# MK_0_2.net
KiCad netlist of a schematic drawn in Altium Designer
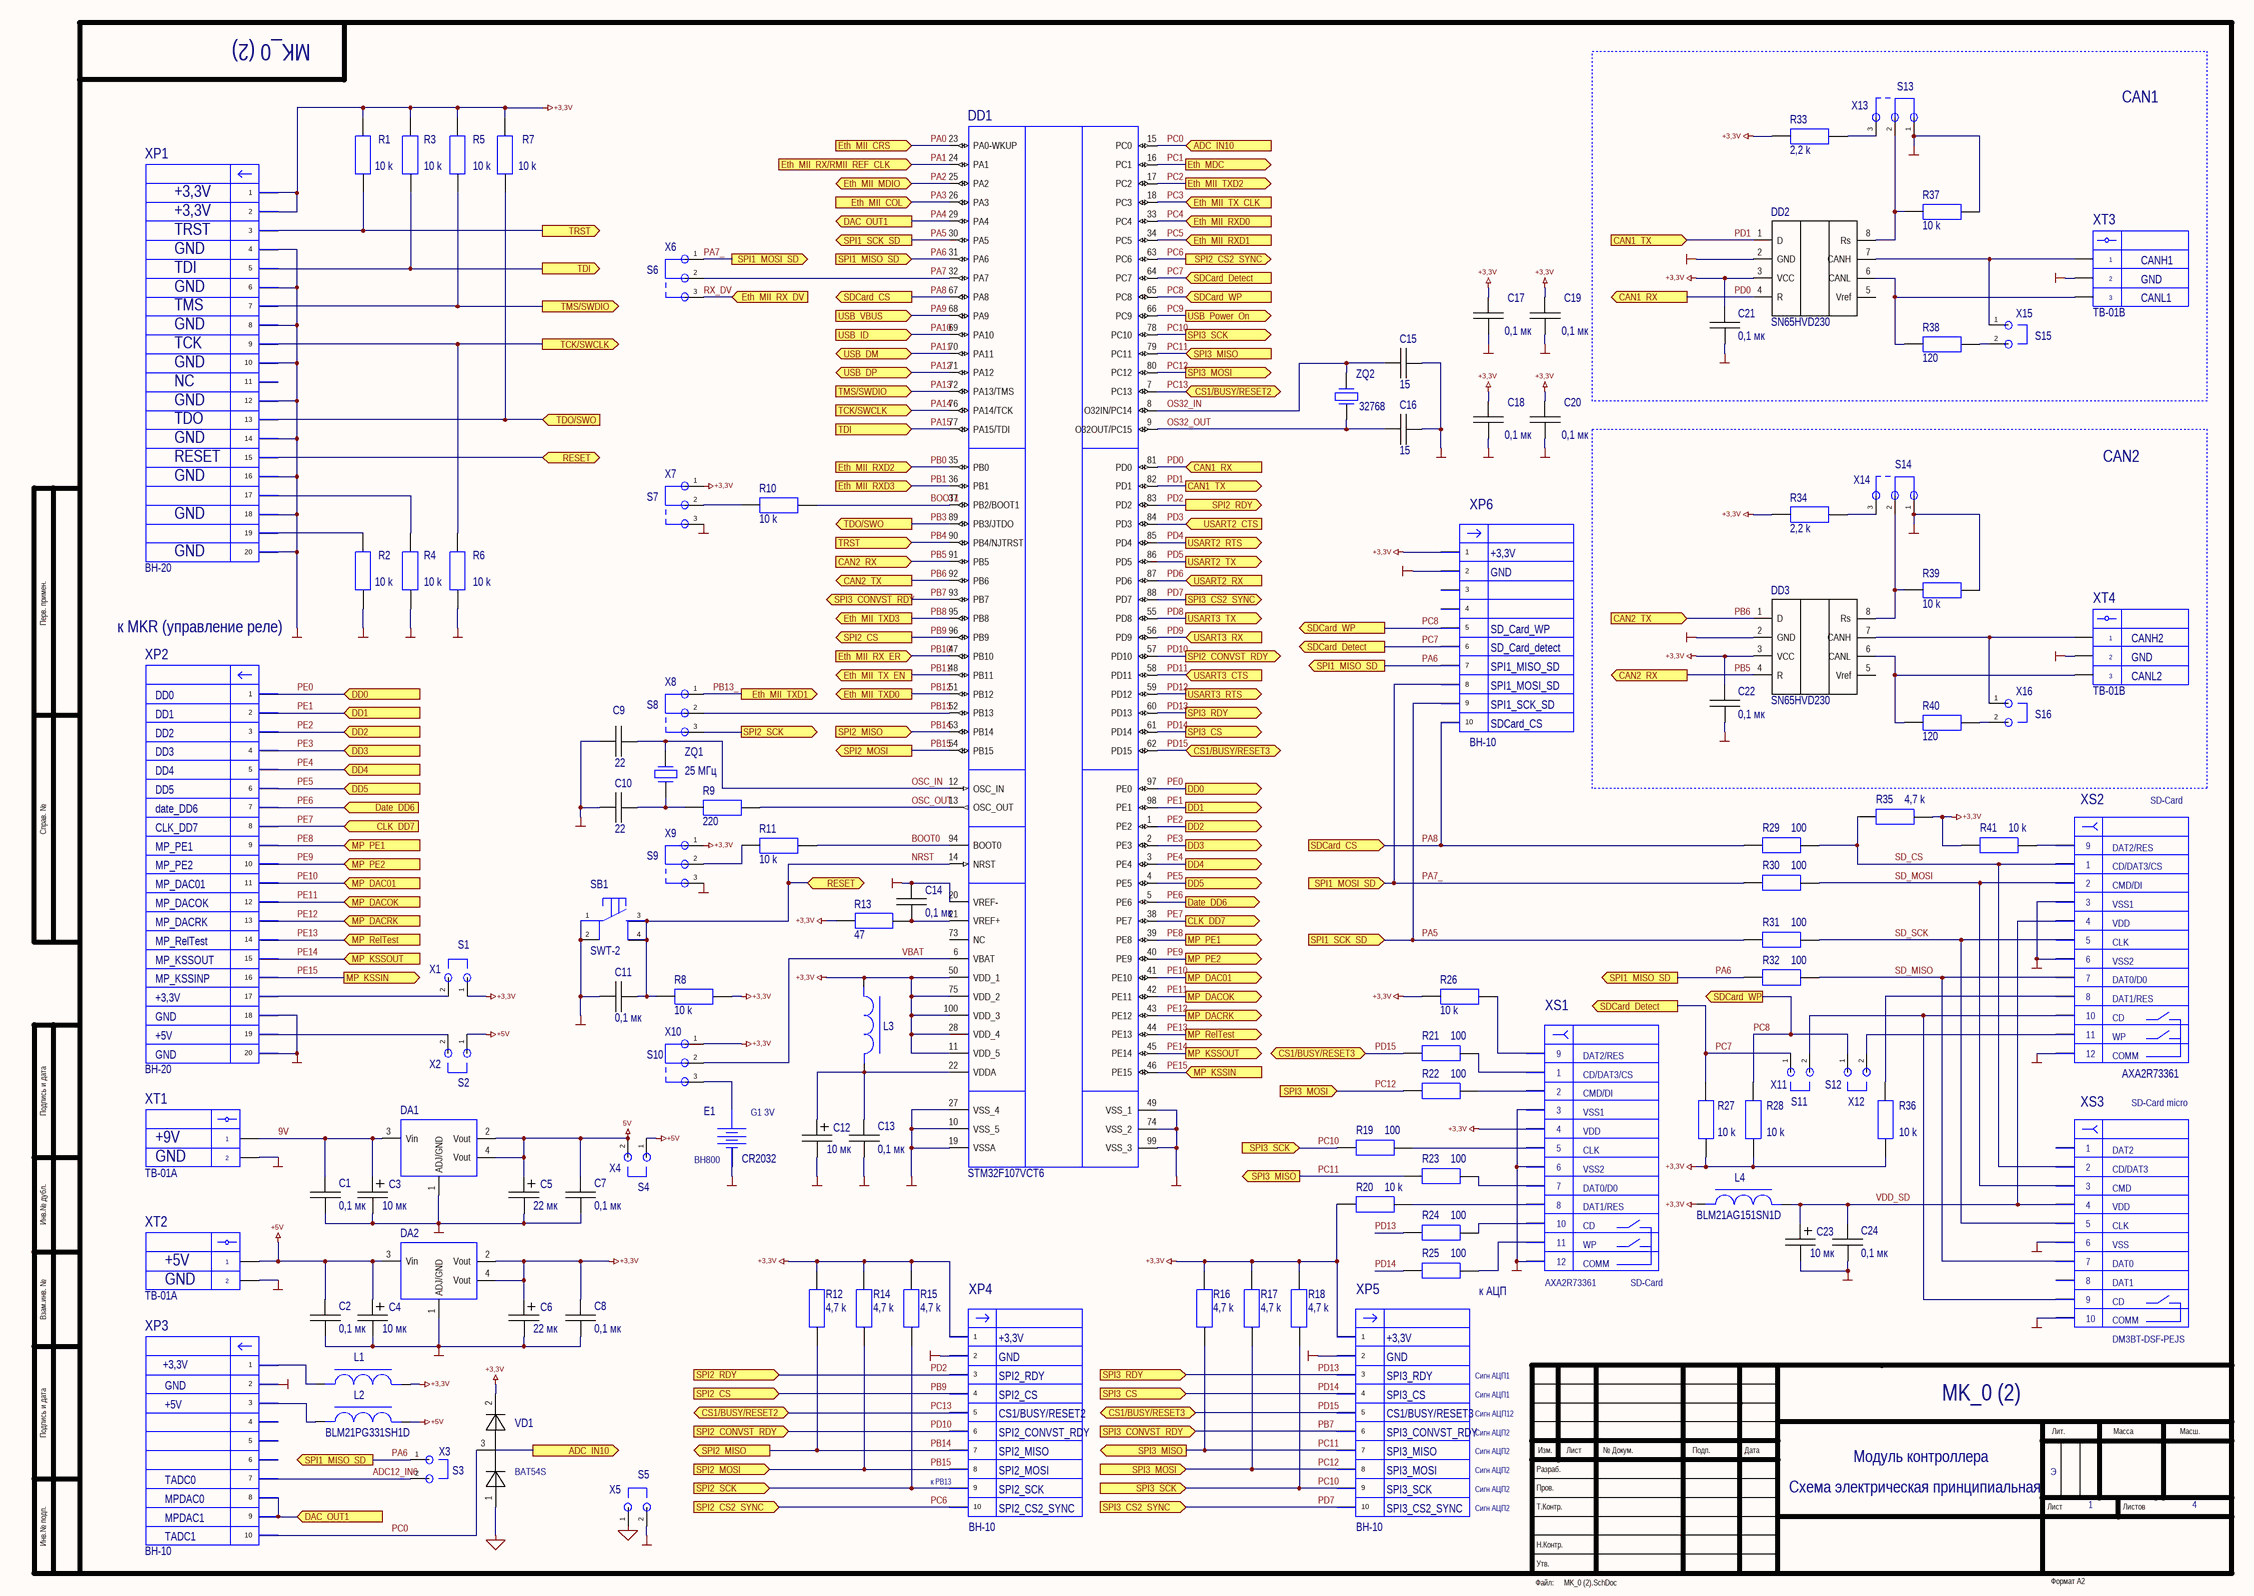
[diagram p0: MK_0 (2).SchDoc]

(export (version "E")
  (design (tool "Eeschema 10.0.6"))
  (components
    (comp (ref "C1")
      (value "0,1 мк")
      (footprint "CAPC_1206")
      (description "Capasitor")
      (fields (field (name "PART NUMBER") "C"))
      (libsource (lib "RLC_GOST") (part "C"))
    )
    (comp (ref "C2")
      (value "0,1 мк")
      (footprint "CAPC_1206")
      (description "Capasitor")
      (fields (field (name "PART NUMBER") "C"))
      (libsource (lib "RLC_GOST") (part "C"))
    )
    (comp (ref "C3")
      (value "10 мк")
      (footprint "3216")
      (description "Capasitor_polar")
      (fields (field (name "PART NUMBER") "CapPol"))
      (libsource (lib "RLC_GOST") (part "CapPol"))
    )
    (comp (ref "C4")
      (value "10 мк")
      (footprint "3216")
      (description "Capasitor_polar")
      (fields (field (name "PART NUMBER") "CapPol"))
      (libsource (lib "RLC_GOST") (part "CapPol"))
    )
    (comp (ref "C5")
      (value "22 мк")
      (footprint "3216")
      (description "Capasitor_polar")
      (fields (field (name "PART NUMBER") "CapPol"))
      (libsource (lib "RLC_GOST") (part "CapPol"))
    )
    (comp (ref "C6")
      (value "22 мк")
      (footprint "3216")
      (description "Capasitor_polar")
      (fields (field (name "PART NUMBER") "CapPol"))
      (libsource (lib "RLC_GOST") (part "CapPol"))
    )
    (comp (ref "C7")
      (value "0,1 мк")
      (footprint "CAPC_1206")
      (description "Capasitor")
      (fields (field (name "PART NUMBER") "C"))
      (libsource (lib "RLC_GOST") (part "C"))
    )
    (comp (ref "C8")
      (value "0,1 мк")
      (footprint "CAPC_1206")
      (description "Capasitor")
      (fields (field (name "PART NUMBER") "C"))
      (libsource (lib "RLC_GOST") (part "C"))
    )
    (comp (ref "C9")
      (value "22")
      (footprint "CAPC_1206")
      (description "Capasitor")
      (libsource (lib "RLC_GOST") (part "C"))
    )
    (comp (ref "C10")
      (value "22")
      (footprint "CAPC_1206")
      (description "Capasitor")
      (libsource (lib "RLC_GOST") (part "C"))
    )
    (comp (ref "C11")
      (value "0,1 мк")
      (footprint "CAPC_1206")
      (description "Capasitor")
      (libsource (lib "RLC_GOST") (part "C"))
    )
    (comp (ref "C12")
      (value "10 мк")
      (footprint "3216")
      (description "Capasitor_polar")
      (fields (field (name "PART NUMBER") "CapPol"))
      (libsource (lib "RLC_GOST") (part "CapPol"))
    )
    (comp (ref "C13")
      (value "0,1 мк")
      (footprint "CAPC_1206")
      (description "Capasitor")
      (fields (field (name "PART NUMBER") "C"))
      (libsource (lib "RLC_GOST") (part "C"))
    )
    (comp (ref "C14")
      (value "0,1 мк")
      (footprint "CAPC_1206")
      (description "Capasitor")
      (fields (field (name "PART NUMBER") "C"))
      (libsource (lib "RLC_GOST") (part "C"))
    )
    (comp (ref "C15")
      (value "15")
      (footprint "CAPC_1206")
      (description "Capasitor")
      (libsource (lib "RLC_GOST") (part "C"))
    )
    (comp (ref "C16")
      (value "15")
      (footprint "CAPC_1206")
      (description "Capasitor")
      (libsource (lib "RLC_GOST") (part "C"))
    )
    (comp (ref "C17")
      (value "0,1 мк")
      (footprint "CAPC_1206")
      (description "Capasitor")
      (fields (field (name "PART NUMBER") "C"))
      (libsource (lib "RLC_GOST") (part "C"))
    )
    (comp (ref "C18")
      (value "0,1 мк")
      (footprint "CAPC_1206")
      (description "Capasitor")
      (fields (field (name "PART NUMBER") "C"))
      (libsource (lib "RLC_GOST") (part "C"))
    )
    (comp (ref "C19")
      (value "0,1 мк")
      (footprint "CAPC_1206")
      (description "Capasitor")
      (fields (field (name "PART NUMBER") "C"))
      (libsource (lib "RLC_GOST") (part "C"))
    )
    (comp (ref "C20")
      (value "0,1 мк")
      (footprint "CAPC_1206")
      (description "Capasitor")
      (fields (field (name "PART NUMBER") "C"))
      (libsource (lib "RLC_GOST") (part "C"))
    )
    (comp (ref "C21")
      (value "0,1 мк")
      (footprint "CAPC_1206")
      (description "Capasitor")
      (fields (field (name "PART NUMBER") "C"))
      (libsource (lib "RLC_GOST") (part "C"))
    )
    (comp (ref "C22")
      (value "0,1 мк")
      (footprint "CAPC_1206")
      (description "Capasitor")
      (fields (field (name "PART NUMBER") "C"))
      (libsource (lib "RLC_GOST") (part "C"))
    )
    (comp (ref "C23")
      (value "10 мк")
      (footprint "3216")
      (description "Capasitor_polar")
      (fields (field (name "PART NUMBER") "CapPol"))
      (libsource (lib "RLC_GOST") (part "CapPol"))
    )
    (comp (ref "C24")
      (value "0,1 мк")
      (footprint "CAPC_1206")
      (description "Capasitor")
      (fields (field (name "PART NUMBER") "C"))
      (libsource (lib "RLC_GOST") (part "C"))
    )
    (comp (ref "DA1")
      (value "LM1117")
      (footprint "SOT223")
      (description "Positive voltage regulators")
      (fields (field (name "MANUFACTURER") "National Semiconductor"))
      (libsource (lib "Stabil") (part "LM1117"))
    )
    (comp (ref "DA2")
      (value "LM1117")
      (footprint "SOT223")
      (description "Positive voltage regulators")
      (fields (field (name "MANUFACTURER") "National Semiconductor"))
      (libsource (lib "Stabil") (part "LM1117"))
    )
    (comp (ref "DD1")
      (value "STM32F107VCT6")
      (footprint "LQFP100")
      (description "STM32 ARM-based 32-bit MCU with 256 Kbytes Flash, 100-pin LQFP, Industrial Temperature")
      (fields (field (name "PUBLISHER") "Altium Limited"))
      (libsource (lib "STM32") (part "STM32F107VCT6"))
    )
    (comp (ref "DD2")
      (value "SN65HVD230")
      (footprint "SO8")
      (description "CAN transceivers")
      (libsource (lib "CAN") (part "SN65HVD230"))
    )
    (comp (ref "DD3")
      (value "SN65HVD230")
      (footprint "SO8")
      (description "CAN transceivers")
      (libsource (lib "CAN") (part "SN65HVD230"))
    )
    (comp (ref "E1")
      (value "BH800")
      (footprint "BATTERY_20mm")
      (fields (field (name "ALTIUM_VALUE") "CR2032") (field (name "G") "G1 3V"))
      (libsource (lib "Connectors") (part "BH800"))
    )
    (comp (ref "L1")
      (value "BLM21PG331SH1D")
      (footprint "C0805")
      (description "Ferrite bead")
      (libsource (lib "RLC_GOST") (part "B"))
    )
    (comp (ref "L2")
      (value "BLM21PG331SH1D")
      (footprint "C0805")
      (description "Ferrite bead")
      (libsource (lib "RLC_GOST") (part "B"))
    )
    (comp (ref "L3")
      (value "BLM21AG151SN1D")
      (footprint "C0805")
      (description "Ferrite bead")
      (libsource (lib "RLC_GOST") (part "B"))
    )
    (comp (ref "L4")
      (value "BLM21AG151SN1D")
      (footprint "C0805")
      (description "Ferrite bead")
      (libsource (lib "RLC_GOST") (part "B"))
    )
    (comp (ref "R1")
      (value "10 k")
      (footprint "SMD_1206")
      (description "Resistor,2 Pin")
      (libsource (lib "RLC_GOST") (part "R_Gost"))
    )
    (comp (ref "R2")
      (value "10 k")
      (footprint "SMD_1206")
      (description "Resistor,2 Pin")
      (libsource (lib "RLC_GOST") (part "R_Gost"))
    )
    (comp (ref "R3")
      (value "10 k")
      (footprint "SMD_1206")
      (description "Resistor,2 Pin")
      (libsource (lib "RLC_GOST") (part "R_Gost"))
    )
    (comp (ref "R4")
      (value "10 k")
      (footprint "SMD_1206")
      (description "Resistor,2 Pin")
      (libsource (lib "RLC_GOST") (part "R_Gost"))
    )
    (comp (ref "R5")
      (value "10 k")
      (footprint "SMD_1206")
      (description "Resistor,2 Pin")
      (libsource (lib "RLC_GOST") (part "R_Gost"))
    )
    (comp (ref "R6")
      (value "10 k")
      (footprint "SMD_1206")
      (description "Resistor,2 Pin")
      (libsource (lib "RLC_GOST") (part "R_Gost"))
    )
    (comp (ref "R7")
      (value "10 k")
      (footprint "SMD_1206")
      (description "Resistor,2 Pin")
      (libsource (lib "RLC_GOST") (part "R_Gost"))
    )
    (comp (ref "R8")
      (value "10 k")
      (footprint "SMD_1206")
      (description "Resistor,2 Pin")
      (libsource (lib "RLC_GOST") (part "R_Gost"))
    )
    (comp (ref "R9")
      (value "220")
      (footprint "SMD_1206")
      (description "Resistor,2 Pin")
      (libsource (lib "RLC_GOST") (part "R_Gost"))
    )
    (comp (ref "R10")
      (value "10 k")
      (footprint "SMD_1206")
      (description "Resistor,2 Pin")
      (libsource (lib "RLC_GOST") (part "R_Gost"))
    )
    (comp (ref "R11")
      (value "10 k")
      (footprint "SMD_1206")
      (description "Resistor,2 Pin")
      (libsource (lib "RLC_GOST") (part "R_Gost"))
    )
    (comp (ref "R12")
      (value "4,7 k")
      (footprint "SMD_1206")
      (description "Resistor,2 Pin")
      (libsource (lib "RLC_GOST") (part "R_Gost"))
    )
    (comp (ref "R13")
      (value "47")
      (footprint "SMD_1206")
      (description "Resistor,2 Pin")
      (libsource (lib "RLC_GOST") (part "R_Gost"))
    )
    (comp (ref "R14")
      (value "4,7 k")
      (footprint "SMD_1206")
      (description "Resistor,2 Pin")
      (libsource (lib "RLC_GOST") (part "R_Gost"))
    )
    (comp (ref "R15")
      (value "4,7 k")
      (footprint "SMD_1206")
      (description "Resistor,2 Pin")
      (libsource (lib "RLC_GOST") (part "R_Gost"))
    )
    (comp (ref "R16")
      (value "4,7 k")
      (footprint "SMD_1206")
      (description "Resistor,2 Pin")
      (libsource (lib "RLC_GOST") (part "R_Gost"))
    )
    (comp (ref "R17")
      (value "4,7 k")
      (footprint "SMD_1206")
      (description "Resistor,2 Pin")
      (libsource (lib "RLC_GOST") (part "R_Gost"))
    )
    (comp (ref "R18")
      (value "4,7 k")
      (footprint "SMD_1206")
      (description "Resistor,2 Pin")
      (libsource (lib "RLC_GOST") (part "R_Gost"))
    )
    (comp (ref "R19")
      (value "100")
      (footprint "SMD_1206")
      (description "Resistor,2 Pin")
      (libsource (lib "RLC_GOST") (part "R_Gost"))
    )
    (comp (ref "R20")
      (value "10 k")
      (footprint "SMD_1206")
      (description "Resistor,2 Pin")
      (libsource (lib "RLC_GOST") (part "R_Gost"))
    )
    (comp (ref "R21")
      (value "100")
      (footprint "SMD_1206")
      (description "Resistor,2 Pin")
      (libsource (lib "RLC_GOST") (part "R_Gost"))
    )
    (comp (ref "R22")
      (value "100")
      (footprint "SMD_1206")
      (description "Resistor,2 Pin")
      (libsource (lib "RLC_GOST") (part "R_Gost"))
    )
    (comp (ref "R23")
      (value "100")
      (footprint "SMD_1206")
      (description "Resistor,2 Pin")
      (libsource (lib "RLC_GOST") (part "R_Gost"))
    )
    (comp (ref "R24")
      (value "100")
      (footprint "SMD_1206")
      (description "Resistor,2 Pin")
      (libsource (lib "RLC_GOST") (part "R_Gost"))
    )
    (comp (ref "R25")
      (value "100")
      (footprint "SMD_1206")
      (description "Resistor,2 Pin")
      (libsource (lib "RLC_GOST") (part "R_Gost"))
    )
    (comp (ref "R26")
      (value "10 k")
      (footprint "SMD_1206")
      (description "Resistor,2 Pin")
      (libsource (lib "RLC_GOST") (part "R_Gost"))
    )
    (comp (ref "R27")
      (value "10 k")
      (footprint "SMD_1206")
      (description "Resistor,2 Pin")
      (libsource (lib "RLC_GOST") (part "R_Gost"))
    )
    (comp (ref "R28")
      (value "10 k")
      (footprint "SMD_1206")
      (description "Resistor,2 Pin")
      (libsource (lib "RLC_GOST") (part "R_Gost"))
    )
    (comp (ref "R29")
      (value "100")
      (footprint "SMD_1206")
      (description "Resistor,2 Pin")
      (libsource (lib "RLC_GOST") (part "R_Gost"))
    )
    (comp (ref "R30")
      (value "100")
      (footprint "SMD_1206")
      (description "Resistor,2 Pin")
      (libsource (lib "RLC_GOST") (part "R_Gost"))
    )
    (comp (ref "R31")
      (value "100")
      (footprint "SMD_1206")
      (description "Resistor,2 Pin")
      (libsource (lib "RLC_GOST") (part "R_Gost"))
    )
    (comp (ref "R32")
      (value "100")
      (footprint "SMD_1206")
      (description "Resistor,2 Pin")
      (libsource (lib "RLC_GOST") (part "R_Gost"))
    )
    (comp (ref "R33")
      (value "2,2 k")
      (footprint "SMD_1206")
      (description "Resistor,2 Pin")
      (libsource (lib "RLC_GOST") (part "R_Gost"))
    )
    (comp (ref "R34")
      (value "2,2 k")
      (footprint "SMD_1206")
      (description "Resistor,2 Pin")
      (libsource (lib "RLC_GOST") (part "R_Gost"))
    )
    (comp (ref "R35")
      (value "4,7 k")
      (footprint "SMD_1206")
      (description "Resistor,2 Pin")
      (libsource (lib "RLC_GOST") (part "R_Gost"))
    )
    (comp (ref "R36")
      (value "10 k")
      (footprint "SMD_1206")
      (description "Resistor,2 Pin")
      (libsource (lib "RLC_GOST") (part "R_Gost"))
    )
    (comp (ref "R37")
      (value "10 k")
      (footprint "SMD_1206")
      (description "Resistor,2 Pin")
      (libsource (lib "RLC_GOST") (part "R_Gost"))
    )
    (comp (ref "R38")
      (value "120")
      (footprint "SMD_1206")
      (description "Resistor,2 Pin")
      (libsource (lib "RLC_GOST") (part "R_Gost"))
    )
    (comp (ref "R39")
      (value "10 k")
      (footprint "SMD_1206")
      (description "Resistor,2 Pin")
      (libsource (lib "RLC_GOST") (part "R_Gost"))
    )
    (comp (ref "R40")
      (value "120")
      (footprint "SMD_1206")
      (description "Resistor,2 Pin")
      (libsource (lib "RLC_GOST") (part "R_Gost"))
    )
    (comp (ref "R41")
      (value "10 k")
      (footprint "SMD_1206")
      (description "Resistor,2 Pin")
      (libsource (lib "RLC_GOST") (part "R_Gost"))
    )
    (comp (ref "SB1")
      (value "SWT-2")
      (footprint "SWT2")
      (description "SWT-2, key")
      (libsource (lib "Keys") (part "SWT-2"))
    )
    (comp (ref "VD1")
      (value "BAT54S")
      (footprint "SOT23")
      (description "Diod Schottky, 3 pin")
      (fields (field (name "MANUFACTURER") "Fairchild"))
      (libsource (lib "Diod") (part "BS40-04"))
    )
    (comp (ref "X1")
      (value "PLS-02")
      (footprint "PLS-2")
      (fields (field (name "JAMPER") "S1"))
      (libsource (lib "Connectors") (part "J2"))
    )
    (comp (ref "X2")
      (value "PLS-02")
      (footprint "PLS-2")
      (fields (field (name "JAMPER") "S2"))
      (libsource (lib "Connectors") (part "J2"))
    )
    (comp (ref "X3")
      (value "PLS-02")
      (footprint "PLS-2")
      (fields (field (name "JAMPER") "S3"))
      (libsource (lib "Connectors") (part "J2"))
    )
    (comp (ref "X4")
      (value "PLS-02")
      (footprint "PLS-2")
      (fields (field (name "JAMPER") "S4"))
      (libsource (lib "Connectors") (part "J2"))
    )
    (comp (ref "X5")
      (value "PLS-02")
      (footprint "PLS-2")
      (fields (field (name "JAMPER") "S5"))
      (libsource (lib "Connectors") (part "J2"))
    )
    (comp (ref "X6")
      (value "PLS-03")
      (footprint "PLS-3")
      (fields (field (name "JAMPER") "S6"))
      (libsource (lib "Connectors") (part "J3"))
    )
    (comp (ref "X7")
      (value "PLS-03")
      (footprint "PLS-3")
      (fields (field (name "JAMPER") "S7"))
      (libsource (lib "Connectors") (part "J3"))
    )
    (comp (ref "X8")
      (value "PLS-03")
      (footprint "PLS-3")
      (fields (field (name "JAMPER") "S8"))
      (libsource (lib "Connectors") (part "J3"))
    )
    (comp (ref "X9")
      (value "PLS-03")
      (footprint "PLS-3")
      (fields (field (name "JAMPER") "S9"))
      (libsource (lib "Connectors") (part "J3"))
    )
    (comp (ref "X10")
      (value "PLS-03")
      (footprint "PLS-3")
      (fields (field (name "JAMPER") "S10"))
      (libsource (lib "Connectors") (part "J3"))
    )
    (comp (ref "X11")
      (value "PLS-02")
      (footprint "PLS-2")
      (fields (field (name "JAMPER") "S11"))
      (libsource (lib "Connectors") (part "J2"))
    )
    (comp (ref "X12")
      (value "PLS-02")
      (footprint "PLS-2")
      (fields (field (name "JAMPER") "S12"))
      (libsource (lib "Connectors") (part "J2"))
    )
    (comp (ref "X13")
      (value "PLS-03")
      (footprint "PLS-3")
      (fields (field (name "JAMPER") "S13"))
      (libsource (lib "Connectors") (part "J3"))
    )
    (comp (ref "X14")
      (value "PLS-03")
      (footprint "PLS-3")
      (fields (field (name "JAMPER") "S14"))
      (libsource (lib "Connectors") (part "J3"))
    )
    (comp (ref "X15")
      (value "PLS-02")
      (footprint "PLS-2")
      (fields (field (name "JAMPER") "S15"))
      (libsource (lib "Connectors") (part "J2"))
    )
    (comp (ref "X16")
      (value "PLS-02")
      (footprint "PLS-2")
      (fields (field (name "JAMPER") "S16"))
      (libsource (lib "Connectors") (part "J2"))
    )
    (comp (ref "XP1") (value "BH-20") (footprint "PLD-20") (libsource (lib "Connectors") (part "BH-20")))
    (comp (ref "XP2") (value "BH-20") (footprint "PLD-20") (libsource (lib "Connectors") (part "BH-20")))
    (comp (ref "XP3") (value "BH-10") (footprint "PLD-10") (libsource (lib "Connectors") (part "BH-10")))
    (comp (ref "XP4") (value "BH-10") (footprint "PLD-10") (libsource (lib "Connectors") (part "BH-10")))
    (comp (ref "XP5") (value "BH-10") (footprint "PLD-10") (libsource (lib "Connectors") (part "BH-10")))
    (comp (ref "XP6") (value "BH-10") (footprint "PLD-10") (libsource (lib "Connectors") (part "BH-10")))
    (comp (ref "XS1")
      (value "AXA2R73361")
      (footprint "SD_AXA2R")
      (description "SD-card socket")
      (fields (field (name "FUNCTION") "SD-Card"))
      (libsource (lib "Connectors") (part "SDcard"))
    )
    (comp (ref "XS2")
      (value "AXA2R73361")
      (footprint "SD_AXA2R")
      (description "SD-card socket")
      (fields (field (name "FUNCTION") "SD-Card"))
      (libsource (lib "Connectors") (part "SDcard"))
    )
    (comp (ref "XS3")
      (value "DM3BT-DSF-PEJS")
      (footprint "DM3BT-DSF-PEJS")
      (description "SD-card socket")
      (fields (field (name "FUNCTION") "SD-Card micro"))
      (libsource (lib "Connectors") (part "MicroSD"))
    )
    (comp (ref "XT1") (value "TB-01A") (footprint "TB-01A") (libsource (lib "Connectors") (part "TB-01A")))
    (comp (ref "XT2") (value "TB-01A") (footprint "TB-01A") (libsource (lib "Connectors") (part "TB-01A")))
    (comp (ref "XT3") (value "TB-01B") (footprint "TB-01B") (libsource (lib "Connectors") (part "TB-01B")))
    (comp (ref "XT4") (value "TB-01B") (footprint "TB-01B") (libsource (lib "Connectors") (part "TB-01B")))
    (comp (ref "ZQ1")
      (value "25 МГц")
      (footprint "HC-49U_5mm")
      (description "OSC")
      (libsource (lib "Resonators") (part "OSC"))
    )
    (comp (ref "ZQ2")
      (value "32768")
      (footprint "DT-38P")
      (description "OSC")
      (libsource (lib "Resonators") (part "OSC"))
    )
  )
  (nets
    (net (code "1") (name "+3,3V") (class "Default")
      (node (ref "C17") (pin "1") (pinfunction "1_1") (pintype "passive"))
      (node (ref "C18") (pin "1") (pinfunction "1_1") (pintype "passive"))
      (node (ref "C19") (pin "1") (pinfunction "1_1") (pintype "passive"))
      (node (ref "C20") (pin "1") (pinfunction "1_1") (pintype "passive"))
      (node (ref "C21") (pin "1") (pinfunction "1_1") (pintype "passive"))
      (node (ref "C22") (pin "1") (pinfunction "1_1") (pintype "passive"))
      (node (ref "C6") (pin "1") (pinfunction "+_1") (pintype "passive"))
      (node (ref "C8") (pin "1") (pinfunction "1_1") (pintype "passive"))
      (node (ref "DA2") (pin "2") (pinfunction "Vout_2") (pintype "power_in"))
      (node (ref "DA2") (pin "4") (pinfunction "Vout_4") (pintype "passive"))
      (node (ref "DD1") (pin "100") (pinfunction "VDD_3_100") (pintype "power_in"))
      (node (ref "DD1") (pin "11") (pinfunction "VDD_5_11") (pintype "power_in"))
      (node (ref "DD1") (pin "28") (pinfunction "VDD_4_28") (pintype "power_in"))
      (node (ref "DD1") (pin "50") (pinfunction "VDD_1_50") (pintype "power_in"))
      (node (ref "DD1") (pin "75") (pinfunction "VDD_2_75") (pintype "power_in"))
      (node (ref "DD2") (pin "3") (pinfunction "VCC_3") (pintype "power_in"))
      (node (ref "DD3") (pin "3") (pinfunction "VCC_3") (pintype "power_in"))
      (node (ref "L1") (pin "2") (pinfunction "2_2") (pintype "passive"))
      (node (ref "L3") (pin "1") (pinfunction "1_1") (pintype "passive"))
      (node (ref "L4") (pin "1") (pinfunction "1_1") (pintype "passive"))
      (node (ref "R1") (pin "2") (pinfunction "2_2") (pintype "passive"))
      (node (ref "R12") (pin "2") (pinfunction "2_2") (pintype "passive"))
      (node (ref "R13") (pin "2") (pinfunction "2_2") (pintype "passive"))
      (node (ref "R14") (pin "2") (pinfunction "2_2") (pintype "passive"))
      (node (ref "R15") (pin "2") (pinfunction "2_2") (pintype "passive"))
      (node (ref "R16") (pin "2") (pinfunction "2_2") (pintype "passive"))
      (node (ref "R17") (pin "2") (pinfunction "2_2") (pintype "passive"))
      (node (ref "R18") (pin "2") (pinfunction "2_2") (pintype "passive"))
      (node (ref "R20") (pin "2") (pinfunction "2_2") (pintype "passive"))
      (node (ref "R26") (pin "1") (pinfunction "1_1") (pintype "passive"))
      (node (ref "R27") (pin "2") (pinfunction "2_2") (pintype "passive"))
      (node (ref "R28") (pin "2") (pinfunction "2_2") (pintype "passive"))
      (node (ref "R3") (pin "2") (pinfunction "2_2") (pintype "passive"))
      (node (ref "R33") (pin "1") (pinfunction "1_1") (pintype "passive"))
      (node (ref "R34") (pin "1") (pinfunction "1_1") (pintype "passive"))
      (node (ref "R35") (pin "1") (pinfunction "1_1") (pintype "passive"))
      (node (ref "R36") (pin "2") (pinfunction "2_2") (pintype "passive"))
      (node (ref "R41") (pin "2") (pinfunction "2_2") (pintype "passive"))
      (node (ref "R5") (pin "2") (pinfunction "2_2") (pintype "passive"))
      (node (ref "R7") (pin "2") (pinfunction "2_2") (pintype "passive"))
      (node (ref "R8") (pin "2") (pinfunction "2_2") (pintype "passive"))
      (node (ref "VD1") (pin "2") (pinfunction "-_2") (pintype "passive"))
      (node (ref "X1") (pin "1") (pinfunction "1_1") (pintype "passive"))
      (node (ref "X10") (pin "1") (pinfunction "1_1") (pintype "passive"))
      (node (ref "X7") (pin "1") (pinfunction "1_1") (pintype "passive"))
      (node (ref "X9") (pin "1") (pinfunction "1_1") (pintype "passive"))
      (node (ref "XP1") (pin "1") (pinfunction "1_1") (pintype "passive"))
      (node (ref "XP1") (pin "2") (pinfunction "2_2") (pintype "passive"))
      (node (ref "XP4") (pin "1") (pinfunction "1_1") (pintype "passive"))
      (node (ref "XP5") (pin "1") (pinfunction "1_1") (pintype "passive"))
      (node (ref "XP6") (pin "1") (pinfunction "1_1") (pintype "passive"))
      (node (ref "XS1") (pin "4") (pinfunction "4_4") (pintype "passive"))
    )
    (net (code "2") (name "+5V") (class "Default")
      (node (ref "C2") (pin "1") (pinfunction "1_1") (pintype "passive"))
      (node (ref "C4") (pin "1") (pinfunction "+_1") (pintype "passive"))
      (node (ref "DA2") (pin "3") (pinfunction "Vin_3") (pintype "power_in"))
      (node (ref "L2") (pin "2") (pinfunction "2_2") (pintype "passive"))
      (node (ref "X2") (pin "1") (pinfunction "1_1") (pintype "passive"))
      (node (ref "X4") (pin "1") (pinfunction "1_1") (pintype "passive"))
      (node (ref "XT2") (pin "1") (pintype "passive"))
    )
    (net (code "3") (name "/9V") (class "Default")
      (node (ref "C1") (pin "1") (pinfunction "1_1") (pintype "passive"))
      (node (ref "C3") (pin "1") (pinfunction "+_1") (pintype "passive"))
      (node (ref "DA1") (pin "3") (pinfunction "Vin_3") (pintype "power_in"))
      (node (ref "XT1") (pin "1") (pintype "passive"))
    )
    (net (code "4") (name "/ADC12_IN6") (class "Default")
      (node (ref "X3") (pin "2") (pinfunction "2_2") (pintype "passive"))
      (node (ref "XP3") (pin "7") (pinfunction "7_7") (pintype "passive"))
    )
    (net (code "5") (name "/BOOT0") (class "Default")
      (node (ref "DD1") (pin "94") (pinfunction "BOOT0_94") (pintype "passive"))
      (node (ref "R11") (pin "2") (pinfunction "2_2") (pintype "passive"))
    )
    (net (code "6") (name "/BOOT1") (class "Default")
      (node (ref "DD1") (pin "37") (pinfunction "PB2/BOOT1_37") (pintype "bidirectional"))
      (node (ref "R10") (pin "2") (pinfunction "2_2") (pintype "passive"))
    )
    (net (code "7") (name "/NRST") (class "Default")
      (node (ref "C11") (pin "2") (pinfunction "2_2") (pintype "passive"))
      (node (ref "DD1") (pin "14") (pinfunction "NRST_14") (pintype "input"))
      (node (ref "R8") (pin "1") (pinfunction "1_1") (pintype "passive"))
      (node (ref "SB1") (pin "3") (pinfunction "3_3") (pintype "passive"))
      (node (ref "SB1") (pin "4") (pinfunction "4_4") (pintype "passive"))
      (node (ref "XP1") (pin "15") (pinfunction "15_15") (pintype "passive"))
    )
    (net (code "8") (name "/OS32_IN") (class "Default")
      (node (ref "C15") (pin "1") (pinfunction "1_1") (pintype "passive"))
      (node (ref "DD1") (pin "8") (pinfunction "O32IN/PC14_8") (pintype "bidirectional"))
      (node (ref "ZQ2") (pin "1") (pinfunction "1_1") (pintype "passive"))
    )
    (net (code "9") (name "/OS32_OUT") (class "Default")
      (node (ref "C16") (pin "1") (pinfunction "1_1") (pintype "passive"))
      (node (ref "DD1") (pin "9") (pinfunction "O32OUT/PC15_9") (pintype "bidirectional"))
      (node (ref "ZQ2") (pin "2") (pinfunction "2_2") (pintype "passive"))
    )
    (net (code "10") (name "/OSC_IN") (class "Default")
      (node (ref "C9") (pin "2") (pinfunction "2_2") (pintype "passive"))
      (node (ref "DD1") (pin "12") (pinfunction "OSC_IN_12") (pintype "input"))
      (node (ref "ZQ1") (pin "2") (pinfunction "2_2") (pintype "passive"))
    )
    (net (code "11") (name "/OSC_OUT") (class "Default")
      (node (ref "DD1") (pin "13") (pinfunction "OSC_OUT_13") (pintype "output"))
      (node (ref "R9") (pin "2") (pinfunction "2_2") (pintype "passive"))
    )
    (net (code "12") (name "/PA0") (class "Default")
      (node (ref "DD1") (pin "23") (pinfunction "PA0-WKUP_23") (pintype "bidirectional"))
    )
    (net (code "13") (name "/PA1") (class "Default")
      (node (ref "DD1") (pin "24") (pinfunction "PA1_24") (pintype "bidirectional"))
    )
    (net (code "14") (name "/PA2") (class "Default")
      (node (ref "DD1") (pin "25") (pinfunction "PA2_25") (pintype "bidirectional"))
    )
    (net (code "15") (name "/PA3") (class "Default")
      (node (ref "DD1") (pin "26") (pinfunction "PA3_26") (pintype "bidirectional"))
    )
    (net (code "16") (name "/PA4") (class "Default")
      (node (ref "DD1") (pin "29") (pinfunction "PA4_29") (pintype "bidirectional"))
      (node (ref "XP3") (pin "8") (pinfunction "8_8") (pintype "passive"))
      (node (ref "XP3") (pin "9") (pinfunction "9_9") (pintype "passive"))
    )
    (net (code "17") (name "/PA5") (class "Default")
      (node (ref "DD1") (pin "30") (pinfunction "PA5_30") (pintype "bidirectional"))
      (node (ref "R31") (pin "2") (pinfunction "2_2") (pintype "passive"))
      (node (ref "XP6") (pin "9") (pinfunction "9_9") (pintype "passive"))
    )
    (net (code "18") (name "/PA6") (class "Default")
      (node (ref "DD1") (pin "31") (pinfunction "PA6_31") (pintype "bidirectional"))
      (node (ref "R32") (pin "2") (pinfunction "2_2") (pintype "passive"))
      (node (ref "X3") (pin "1") (pinfunction "1_1") (pintype "passive"))
      (node (ref "XP6") (pin "7") (pinfunction "7_7") (pintype "passive"))
    )
    (net (code "19") (name "/PA7") (class "Default")
      (node (ref "DD1") (pin "32") (pinfunction "PA7_32") (pintype "bidirectional"))
      (node (ref "X6") (pin "2") (pinfunction "2_2") (pintype "passive"))
    )
    (net (code "20") (name "/PA7_") (class "Default")
      (node (ref "R30") (pin "2") (pinfunction "2_2") (pintype "passive"))
      (node (ref "X6") (pin "1") (pinfunction "1_1") (pintype "passive"))
      (node (ref "XP6") (pin "8") (pinfunction "8_8") (pintype "passive"))
    )
    (net (code "21") (name "/PA8") (class "Default")
      (node (ref "DD1") (pin "67") (pinfunction "PA8_67") (pintype "bidirectional"))
      (node (ref "R29") (pin "2") (pinfunction "2_2") (pintype "passive"))
      (node (ref "XP6") (pin "10") (pinfunction "10_10") (pintype "passive"))
    )
    (net (code "22") (name "/PA9") (class "Default")
      (node (ref "DD1") (pin "68") (pinfunction "PA9_68") (pintype "bidirectional"))
    )
    (net (code "23") (name "/PA10") (class "Default")
      (node (ref "DD1") (pin "69") (pinfunction "PA10_69") (pintype "bidirectional"))
    )
    (net (code "24") (name "/PA11") (class "Default")
      (node (ref "DD1") (pin "70") (pinfunction "PA11_70") (pintype "bidirectional"))
    )
    (net (code "25") (name "/PA12") (class "Default")
      (node (ref "DD1") (pin "71") (pinfunction "PA12_71") (pintype "bidirectional"))
    )
    (net (code "26") (name "/PA13") (class "Default")
      (node (ref "DD1") (pin "72") (pinfunction "PA13/TMS_72") (pintype "bidirectional"))
      (node (ref "R5") (pin "1") (pinfunction "1_1") (pintype "passive"))
      (node (ref "XP1") (pin "7") (pinfunction "7_7") (pintype "passive"))
    )
    (net (code "27") (name "/PA14") (class "Default")
      (node (ref "DD1") (pin "76") (pinfunction "PA14/TCK_76") (pintype "bidirectional"))
      (node (ref "R6") (pin "2") (pinfunction "2_2") (pintype "passive"))
      (node (ref "XP1") (pin "9") (pinfunction "9_9") (pintype "passive"))
    )
    (net (code "28") (name "/PA15") (class "Default")
      (node (ref "DD1") (pin "77") (pinfunction "PA15/TDI_77") (pintype "bidirectional"))
      (node (ref "R3") (pin "1") (pinfunction "1_1") (pintype "passive"))
      (node (ref "XP1") (pin "5") (pinfunction "5_5") (pintype "passive"))
    )
    (net (code "29") (name "/PB0") (class "Default")
      (node (ref "DD1") (pin "35") (pinfunction "PB0_35") (pintype "bidirectional"))
    )
    (net (code "30") (name "/PB1") (class "Default")
      (node (ref "DD1") (pin "36") (pinfunction "PB1_36") (pintype "bidirectional"))
    )
    (net (code "31") (name "/PB3") (class "Default")
      (node (ref "DD1") (pin "89") (pinfunction "PB3/JTDO_89") (pintype "bidirectional"))
      (node (ref "R7") (pin "1") (pinfunction "1_1") (pintype "passive"))
      (node (ref "XP1") (pin "13") (pinfunction "13_13") (pintype "passive"))
    )
    (net (code "32") (name "/PB4") (class "Default")
      (node (ref "DD1") (pin "90") (pinfunction "PB4/NJTRST_90") (pintype "bidirectional"))
      (node (ref "R1") (pin "1") (pinfunction "1_1") (pintype "passive"))
      (node (ref "XP1") (pin "3") (pinfunction "3_3") (pintype "passive"))
    )
    (net (code "33") (name "/PB5") (class "Default")
      (node (ref "DD1") (pin "91") (pinfunction "PB5_91") (pintype "bidirectional"))
      (node (ref "DD3") (pin "4") (pinfunction "R_4") (pintype "passive"))
    )
    (net (code "34") (name "/PB6") (class "Default")
      (node (ref "DD1") (pin "92") (pinfunction "PB6_92") (pintype "bidirectional"))
      (node (ref "DD3") (pin "1") (pinfunction "D_1") (pintype "passive"))
    )
    (net (code "35") (name "/PB7") (class "Default")
      (node (ref "DD1") (pin "93") (pinfunction "PB7_93") (pintype "bidirectional"))
      (node (ref "XP5") (pin "6") (pinfunction "6_6") (pintype "passive"))
    )
    (net (code "36") (name "/PB8") (class "Default")
      (node (ref "DD1") (pin "95") (pinfunction "PB8_95") (pintype "bidirectional"))
    )
    (net (code "37") (name "/PB9") (class "Default")
      (node (ref "DD1") (pin "96") (pinfunction "PB9_96") (pintype "bidirectional"))
      (node (ref "XP4") (pin "4") (pinfunction "4_4") (pintype "passive"))
    )
    (net (code "38") (name "/PB10") (class "Default")
      (node (ref "DD1") (pin "47") (pinfunction "PB10_47") (pintype "bidirectional"))
    )
    (net (code "39") (name "/PB11") (class "Default")
      (node (ref "DD1") (pin "48") (pinfunction "PB11_48") (pintype "bidirectional"))
    )
    (net (code "40") (name "/PB12") (class "Default")
      (node (ref "DD1") (pin "51") (pinfunction "PB12_51") (pintype "bidirectional"))
    )
    (net (code "41") (name "/PB13") (class "Default")
      (node (ref "DD1") (pin "52") (pinfunction "PB13_52") (pintype "bidirectional"))
      (node (ref "X8") (pin "2") (pinfunction "2_2") (pintype "passive"))
    )
    (net (code "42") (name "/PB13_") (class "Default")
      (node (ref "X8") (pin "1") (pinfunction "1_1") (pintype "passive"))
    )
    (net (code "43") (name "/PB14") (class "Default")
      (node (ref "DD1") (pin "53") (pinfunction "PB14_53") (pintype "bidirectional"))
      (node (ref "R12") (pin "1") (pinfunction "1_1") (pintype "passive"))
      (node (ref "XP4") (pin "7") (pinfunction "7_7") (pintype "passive"))
    )
    (net (code "44") (name "/PB15") (class "Default")
      (node (ref "DD1") (pin "54") (pinfunction "PB15_54") (pintype "bidirectional"))
      (node (ref "R14") (pin "1") (pinfunction "1_1") (pintype "passive"))
      (node (ref "XP4") (pin "8") (pinfunction "8_8") (pintype "passive"))
    )
    (net (code "45") (name "/PC0") (class "Default")
      (node (ref "DD1") (pin "15") (pinfunction "PC0_15") (pintype "bidirectional"))
      (node (ref "VD1") (pin "3") (pintype "passive"))
      (node (ref "XP3") (pin "10") (pinfunction "10_10") (pintype "passive"))
    )
    (net (code "46") (name "/PC1") (class "Default")
      (node (ref "DD1") (pin "16") (pinfunction "PC1_16") (pintype "bidirectional"))
    )
    (net (code "47") (name "/PC2") (class "Default")
      (node (ref "DD1") (pin "17") (pinfunction "PC2_17") (pintype "bidirectional"))
    )
    (net (code "48") (name "/PC3") (class "Default")
      (node (ref "DD1") (pin "18") (pinfunction "PC3_18") (pintype "bidirectional"))
    )
    (net (code "49") (name "/PC4") (class "Default")
      (node (ref "DD1") (pin "33") (pinfunction "PC4_33") (pintype "bidirectional"))
    )
    (net (code "50") (name "/PC5") (class "Default")
      (node (ref "DD1") (pin "34") (pinfunction "PC5_34") (pintype "bidirectional"))
    )
    (net (code "51") (name "/PC6") (class "Default")
      (node (ref "DD1") (pin "63") (pinfunction "PC6_63") (pintype "bidirectional"))
      (node (ref "XP4") (pin "10") (pinfunction "10_10") (pintype "passive"))
    )
    (net (code "52") (name "/PC7") (class "Default")
      (node (ref "DD1") (pin "64") (pinfunction "PC7_64") (pintype "bidirectional"))
      (node (ref "R27") (pin "1") (pinfunction "1_1") (pintype "passive"))
      (node (ref "X11") (pin "1") (pinfunction "1_1") (pintype "passive"))
      (node (ref "XP6") (pin "6") (pinfunction "6_6") (pintype "passive"))
    )
    (net (code "53") (name "/PC8") (class "Default")
      (node (ref "DD1") (pin "65") (pinfunction "PC8_65") (pintype "bidirectional"))
      (node (ref "R28") (pin "1") (pinfunction "1_1") (pintype "passive"))
      (node (ref "X12") (pin "1") (pinfunction "1_1") (pintype "passive"))
      (node (ref "XP6") (pin "5") (pinfunction "5_5") (pintype "passive"))
    )
    (net (code "54") (name "/PC9") (class "Default")
      (node (ref "DD1") (pin "66") (pinfunction "PC9_66") (pintype "bidirectional"))
    )
    (net (code "55") (name "/PC10") (class "Default")
      (node (ref "DD1") (pin "78") (pinfunction "PC10_78") (pintype "bidirectional"))
      (node (ref "R18") (pin "1") (pinfunction "1_1") (pintype "passive"))
      (node (ref "R19") (pin "2") (pinfunction "2_2") (pintype "passive"))
      (node (ref "XP5") (pin "9") (pinfunction "9_9") (pintype "passive"))
    )
    (net (code "56") (name "/PC11") (class "Default")
      (node (ref "DD1") (pin "79") (pinfunction "PC11_79") (pintype "bidirectional"))
      (node (ref "R16") (pin "1") (pinfunction "1_1") (pintype "passive"))
      (node (ref "R23") (pin "2") (pinfunction "2_2") (pintype "passive"))
      (node (ref "XP5") (pin "7") (pinfunction "7_7") (pintype "passive"))
    )
    (net (code "57") (name "/PC12") (class "Default")
      (node (ref "DD1") (pin "80") (pinfunction "PC12_80") (pintype "bidirectional"))
      (node (ref "R17") (pin "1") (pinfunction "1_1") (pintype "passive"))
      (node (ref "R22") (pin "2") (pinfunction "2_2") (pintype "passive"))
      (node (ref "XP5") (pin "8") (pinfunction "8_8") (pintype "passive"))
    )
    (net (code "58") (name "/PC13") (class "Default")
      (node (ref "DD1") (pin "7") (pinfunction "PC13_7") (pintype "bidirectional"))
      (node (ref "XP4") (pin "5") (pinfunction "5_5") (pintype "passive"))
    )
    (net (code "59") (name "/PD0") (class "Default")
      (node (ref "DD1") (pin "81") (pinfunction "PD0_81") (pintype "bidirectional"))
      (node (ref "DD2") (pin "4") (pinfunction "R_4") (pintype "passive"))
    )
    (net (code "60") (name "/PD1") (class "Default")
      (node (ref "DD1") (pin "82") (pinfunction "PD1_82") (pintype "bidirectional"))
      (node (ref "DD2") (pin "1") (pinfunction "D_1") (pintype "passive"))
    )
    (net (code "61") (name "/PD2") (class "Default")
      (node (ref "DD1") (pin "83") (pinfunction "PD2_83") (pintype "bidirectional"))
      (node (ref "XP4") (pin "3") (pinfunction "3_3") (pintype "passive"))
    )
    (net (code "62") (name "/PD3") (class "Default")
      (node (ref "DD1") (pin "84") (pinfunction "PD3_84") (pintype "bidirectional"))
    )
    (net (code "63") (name "/PD4") (class "Default")
      (node (ref "DD1") (pin "85") (pinfunction "PD4_85") (pintype "bidirectional"))
    )
    (net (code "64") (name "/PD5") (class "Default")
      (node (ref "DD1") (pin "86") (pinfunction "PD5_86") (pintype "bidirectional"))
    )
    (net (code "65") (name "/PD6") (class "Default")
      (node (ref "DD1") (pin "87") (pinfunction "PD6_87") (pintype "bidirectional"))
    )
    (net (code "66") (name "/PD7") (class "Default")
      (node (ref "DD1") (pin "88") (pinfunction "PD7_88") (pintype "bidirectional"))
      (node (ref "XP5") (pin "10") (pinfunction "10_10") (pintype "passive"))
    )
    (net (code "67") (name "/PD8") (class "Default")
      (node (ref "DD1") (pin "55") (pinfunction "PD8_55") (pintype "bidirectional"))
    )
    (net (code "68") (name "/PD9") (class "Default")
      (node (ref "DD1") (pin "56") (pinfunction "PD9_56") (pintype "bidirectional"))
    )
    (net (code "69") (name "/PD10") (class "Default")
      (node (ref "DD1") (pin "57") (pinfunction "PD10_57") (pintype "bidirectional"))
      (node (ref "XP4") (pin "6") (pinfunction "6_6") (pintype "passive"))
    )
    (net (code "70") (name "/PD11") (class "Default")
      (node (ref "DD1") (pin "58") (pinfunction "PD11_58") (pintype "bidirectional"))
    )
    (net (code "71") (name "/PD12") (class "Default")
      (node (ref "DD1") (pin "59") (pinfunction "PD12_59") (pintype "bidirectional"))
    )
    (net (code "72") (name "/PD13") (class "Default")
      (node (ref "DD1") (pin "60") (pinfunction "PD13_60") (pintype "bidirectional"))
      (node (ref "R24") (pin "2") (pinfunction "2_2") (pintype "passive"))
      (node (ref "XP5") (pin "3") (pinfunction "3_3") (pintype "passive"))
    )
    (net (code "73") (name "/PD14") (class "Default")
      (node (ref "DD1") (pin "61") (pinfunction "PD14_61") (pintype "bidirectional"))
      (node (ref "R25") (pin "2") (pinfunction "2_2") (pintype "passive"))
      (node (ref "XP5") (pin "4") (pinfunction "4_4") (pintype "passive"))
    )
    (net (code "74") (name "/PD15") (class "Default")
      (node (ref "DD1") (pin "62") (pinfunction "PD15_62") (pintype "bidirectional"))
      (node (ref "R21") (pin "2") (pinfunction "2_2") (pintype "passive"))
      (node (ref "XP5") (pin "5") (pinfunction "5_5") (pintype "passive"))
    )
    (net (code "75") (name "/PE0") (class "Default")
      (node (ref "DD1") (pin "97") (pinfunction "PE0_97") (pintype "bidirectional"))
      (node (ref "XP2") (pin "1") (pinfunction "1_1") (pintype "passive"))
    )
    (net (code "76") (name "/PE1") (class "Default")
      (node (ref "DD1") (pin "98") (pinfunction "PE1_98") (pintype "bidirectional"))
      (node (ref "XP2") (pin "2") (pinfunction "2_2") (pintype "passive"))
    )
    (net (code "77") (name "/PE2") (class "Default")
      (node (ref "DD1") (pin "1") (pinfunction "PE2_1") (pintype "bidirectional"))
      (node (ref "XP2") (pin "3") (pinfunction "3_3") (pintype "passive"))
    )
    (net (code "78") (name "/PE3") (class "Default")
      (node (ref "DD1") (pin "2") (pinfunction "PE3_2") (pintype "bidirectional"))
      (node (ref "XP2") (pin "4") (pinfunction "4_4") (pintype "passive"))
    )
    (net (code "79") (name "/PE4") (class "Default")
      (node (ref "DD1") (pin "3") (pinfunction "PE4_3") (pintype "bidirectional"))
      (node (ref "XP2") (pin "5") (pinfunction "5_5") (pintype "passive"))
    )
    (net (code "80") (name "/PE5") (class "Default")
      (node (ref "DD1") (pin "4") (pinfunction "PE5_4") (pintype "bidirectional"))
      (node (ref "XP2") (pin "6") (pinfunction "6_6") (pintype "passive"))
    )
    (net (code "81") (name "/PE6") (class "Default")
      (node (ref "DD1") (pin "5") (pinfunction "PE6_5") (pintype "bidirectional"))
      (node (ref "XP2") (pin "7") (pinfunction "7_7") (pintype "passive"))
    )
    (net (code "82") (name "/PE7") (class "Default")
      (node (ref "DD1") (pin "38") (pinfunction "PE7_38") (pintype "bidirectional"))
      (node (ref "XP2") (pin "8") (pinfunction "8_8") (pintype "passive"))
    )
    (net (code "83") (name "/PE8") (class "Default")
      (node (ref "DD1") (pin "39") (pinfunction "PE8_39") (pintype "bidirectional"))
      (node (ref "XP2") (pin "9") (pinfunction "9_9") (pintype "passive"))
    )
    (net (code "84") (name "/PE9") (class "Default")
      (node (ref "DD1") (pin "40") (pinfunction "PE9_40") (pintype "bidirectional"))
      (node (ref "XP2") (pin "10") (pinfunction "10_10") (pintype "passive"))
    )
    (net (code "85") (name "/PE10") (class "Default")
      (node (ref "DD1") (pin "41") (pinfunction "PE10_41") (pintype "bidirectional"))
      (node (ref "XP2") (pin "11") (pinfunction "11_11") (pintype "passive"))
    )
    (net (code "86") (name "/PE11") (class "Default")
      (node (ref "DD1") (pin "42") (pinfunction "PE11_42") (pintype "bidirectional"))
      (node (ref "XP2") (pin "12") (pinfunction "12_12") (pintype "passive"))
    )
    (net (code "87") (name "/PE12") (class "Default")
      (node (ref "DD1") (pin "43") (pinfunction "PE12_43") (pintype "bidirectional"))
      (node (ref "XP2") (pin "13") (pinfunction "13_13") (pintype "passive"))
    )
    (net (code "88") (name "/PE13") (class "Default")
      (node (ref "DD1") (pin "44") (pinfunction "PE13_44") (pintype "bidirectional"))
      (node (ref "XP2") (pin "14") (pinfunction "14_14") (pintype "passive"))
    )
    (net (code "89") (name "/PE14") (class "Default")
      (node (ref "DD1") (pin "45") (pinfunction "PE14_45") (pintype "bidirectional"))
      (node (ref "XP2") (pin "15") (pinfunction "15_15") (pintype "passive"))
    )
    (net (code "90") (name "/PE15") (class "Default")
      (node (ref "DD1") (pin "46") (pinfunction "PE15_46") (pintype "bidirectional"))
      (node (ref "XP2") (pin "16") (pinfunction "16_16") (pintype "passive"))
    )
    (net (code "91") (name "/RX_DV") (class "Default")
      (node (ref "X6") (pin "3") (pinfunction "3_3") (pintype "passive"))
    )
    (net (code "92") (name "/SD_CS") (class "Default")
      (node (ref "R29") (pin "1") (pinfunction "1_1") (pintype "passive"))
      (node (ref "R35") (pin "2") (pinfunction "2_2") (pintype "passive"))
      (node (ref "XS2") (pin "1") (pinfunction "1_1") (pintype "passive"))
      (node (ref "XS3") (pin "2") (pinfunction "2_2") (pintype "passive"))
    )
    (net (code "93") (name "/SD_MISO") (class "Default")
      (node (ref "R32") (pin "1") (pinfunction "1_1") (pintype "passive"))
      (node (ref "XS2") (pin "7") (pinfunction "7_7") (pintype "passive"))
      (node (ref "XS3") (pin "7") (pinfunction "7_7") (pintype "passive"))
    )
    (net (code "94") (name "/SD_MOSI") (class "Default")
      (node (ref "R30") (pin "1") (pinfunction "1_1") (pintype "passive"))
      (node (ref "XS2") (pin "2") (pinfunction "2_2") (pintype "passive"))
      (node (ref "XS3") (pin "3") (pinfunction "3_3") (pintype "passive"))
    )
    (net (code "95") (name "/SD_SCK") (class "Default")
      (node (ref "R31") (pin "1") (pinfunction "1_1") (pintype "passive"))
      (node (ref "XS2") (pin "5") (pinfunction "5_5") (pintype "passive"))
      (node (ref "XS3") (pin "5") (pinfunction "5_5") (pintype "passive"))
    )
    (net (code "96") (name "/SPI2_SCK") (class "Default")
      (node (ref "R15") (pin "1") (pinfunction "1_1") (pintype "passive"))
      (node (ref "X8") (pin "3") (pinfunction "3_3") (pintype "passive"))
      (node (ref "XP4") (pin "9") (pinfunction "9_9") (pintype "passive"))
    )
    (net (code "97") (name "/VBAT") (class "Default")
      (node (ref "DD1") (pin "6") (pinfunction "VBAT_6") (pintype "power_in"))
      (node (ref "X10") (pin "2") (pinfunction "2_2") (pintype "passive"))
    )
    (net (code "98") (name "/VDD_SD") (class "Default")
      (node (ref "C23") (pin "1") (pinfunction "+_1") (pintype "passive"))
      (node (ref "C24") (pin "1") (pinfunction "1_1") (pintype "passive"))
      (node (ref "L4") (pin "2") (pinfunction "2_2") (pintype "passive"))
      (node (ref "XS2") (pin "4") (pinfunction "4_4") (pintype "passive"))
      (node (ref "XS3") (pin "4") (pinfunction "4_4") (pintype "passive"))
    )
    (net (code "99") (name "5V") (class "Default")
      (node (ref "C5") (pin "1") (pinfunction "+_1") (pintype "passive"))
      (node (ref "C7") (pin "1") (pinfunction "1_1") (pintype "passive"))
      (node (ref "DA1") (pin "2") (pinfunction "Vout_2") (pintype "power_in"))
      (node (ref "DA1") (pin "4") (pinfunction "Vout_4") (pintype "passive"))
      (node (ref "X4") (pin "2") (pinfunction "2_2") (pintype "passive"))
    )
    (net (code "100") (name "AGND") (class "Default")
      (node (ref "VD1") (pin "1") (pinfunction "+_1") (pintype "passive"))
      (node (ref "X5") (pin "1") (pinfunction "1_1") (pintype "passive"))
    )
    (net (code "101") (name "GND") (class "Default")
      (node (ref "C1") (pin "2") (pinfunction "2_2") (pintype "passive"))
      (node (ref "C10") (pin "1") (pinfunction "1_1") (pintype "passive"))
      (node (ref "C11") (pin "1") (pinfunction "1_1") (pintype "passive"))
      (node (ref "C12") (pin "2") (pinfunction "-_2") (pintype "passive"))
      (node (ref "C13") (pin "2") (pinfunction "2_2") (pintype "passive"))
      (node (ref "C14") (pin "1") (pinfunction "1_1") (pintype "passive"))
      (node (ref "C15") (pin "2") (pinfunction "2_2") (pintype "passive"))
      (node (ref "C16") (pin "2") (pinfunction "2_2") (pintype "passive"))
      (node (ref "C17") (pin "2") (pinfunction "2_2") (pintype "passive"))
      (node (ref "C18") (pin "2") (pinfunction "2_2") (pintype "passive"))
      (node (ref "C19") (pin "2") (pinfunction "2_2") (pintype "passive"))
      (node (ref "C2") (pin "2") (pinfunction "2_2") (pintype "passive"))
      (node (ref "C20") (pin "2") (pinfunction "2_2") (pintype "passive"))
      (node (ref "C21") (pin "2") (pinfunction "2_2") (pintype "passive"))
      (node (ref "C22") (pin "2") (pinfunction "2_2") (pintype "passive"))
      (node (ref "C23") (pin "2") (pinfunction "-_2") (pintype "passive"))
      (node (ref "C24") (pin "2") (pinfunction "2_2") (pintype "passive"))
      (node (ref "C3") (pin "2") (pinfunction "-_2") (pintype "passive"))
      (node (ref "C4") (pin "2") (pinfunction "-_2") (pintype "passive"))
      (node (ref "C5") (pin "2") (pinfunction "-_2") (pintype "passive"))
      (node (ref "C6") (pin "2") (pinfunction "-_2") (pintype "passive"))
      (node (ref "C7") (pin "2") (pinfunction "2_2") (pintype "passive"))
      (node (ref "C8") (pin "2") (pinfunction "2_2") (pintype "passive"))
      (node (ref "C9") (pin "1") (pinfunction "1_1") (pintype "passive"))
      (node (ref "DA1") (pin "1") (pinfunction "ADJ/GND_1") (pintype "power_in"))
      (node (ref "DA2") (pin "1") (pinfunction "ADJ/GND_1") (pintype "power_in"))
      (node (ref "DD1") (pin "10") (pinfunction "VSS_5_10") (pintype "power_in"))
      (node (ref "DD1") (pin "19") (pinfunction "VSSA_19") (pintype "power_in"))
      (node (ref "DD1") (pin "20") (pinfunction "VREF-_20") (pintype "power_in"))
      (node (ref "DD1") (pin "27") (pinfunction "VSS_4_27") (pintype "power_in"))
      (node (ref "DD1") (pin "49") (pinfunction "VSS_1_49") (pintype "power_in"))
      (node (ref "DD1") (pin "74") (pinfunction "VSS_2_74") (pintype "power_in"))
      (node (ref "DD1") (pin "99") (pinfunction "VSS_3_99") (pintype "power_in"))
      (node (ref "DD2") (pin "2") (pinfunction "GND_2") (pintype "power_in"))
      (node (ref "DD3") (pin "2") (pinfunction "GND_2") (pintype "power_in"))
      (node (ref "E1") (pin "2") (pinfunction "2_2") (pintype "passive"))
      (node (ref "R2") (pin "1") (pinfunction "1_1") (pintype "passive"))
      (node (ref "R37") (pin "2") (pinfunction "2_2") (pintype "passive"))
      (node (ref "R39") (pin "2") (pinfunction "2_2") (pintype "passive"))
      (node (ref "R4") (pin "1") (pinfunction "1_1") (pintype "passive"))
      (node (ref "R6") (pin "1") (pinfunction "1_1") (pintype "passive"))
      (node (ref "SB1") (pin "1") (pinfunction "1_1") (pintype "passive"))
      (node (ref "SB1") (pin "2") (pinfunction "2_2") (pintype "passive"))
      (node (ref "X13") (pin "1") (pinfunction "1_1") (pintype "passive"))
      (node (ref "X14") (pin "1") (pinfunction "1_1") (pintype "passive"))
      (node (ref "X5") (pin "2") (pinfunction "2_2") (pintype "passive"))
      (node (ref "X7") (pin "3") (pinfunction "3_3") (pintype "passive"))
      (node (ref "X9") (pin "3") (pinfunction "3_3") (pintype "passive"))
      (node (ref "XP1") (pin "10") (pinfunction "10_10") (pintype "passive"))
      (node (ref "XP1") (pin "12") (pinfunction "12_12") (pintype "passive"))
      (node (ref "XP1") (pin "14") (pinfunction "14_14") (pintype "passive"))
      (node (ref "XP1") (pin "16") (pinfunction "16_16") (pintype "passive"))
      (node (ref "XP1") (pin "18") (pinfunction "18_18") (pintype "passive"))
      (node (ref "XP1") (pin "20") (pinfunction "20_20") (pintype "passive"))
      (node (ref "XP1") (pin "4") (pinfunction "4_4") (pintype "passive"))
      (node (ref "XP1") (pin "6") (pinfunction "6_6") (pintype "passive"))
      (node (ref "XP1") (pin "8") (pinfunction "8_8") (pintype "passive"))
      (node (ref "XP2") (pin "18") (pinfunction "18_18") (pintype "passive"))
      (node (ref "XP2") (pin "20") (pinfunction "20_20") (pintype "passive"))
      (node (ref "XP3") (pin "2") (pinfunction "2_2") (pintype "passive"))
      (node (ref "XP4") (pin "2") (pinfunction "2_2") (pintype "passive"))
      (node (ref "XP5") (pin "2") (pinfunction "2_2") (pintype "passive"))
      (node (ref "XP6") (pin "2") (pinfunction "2_2") (pintype "passive"))
      (node (ref "XS1") (pin "12") (pinfunction "12_12") (pintype "passive"))
      (node (ref "XS1") (pin "3") (pinfunction "3_3") (pintype "passive"))
      (node (ref "XS1") (pin "6") (pinfunction "6_6") (pintype "passive"))
      (node (ref "XS2") (pin "12") (pinfunction "12_12") (pintype "passive"))
      (node (ref "XS2") (pin "3") (pinfunction "3_3") (pintype "passive"))
      (node (ref "XS2") (pin "6") (pinfunction "6_6") (pintype "passive"))
      (node (ref "XS3") (pin "10") (pinfunction "10_10") (pintype "passive"))
      (node (ref "XS3") (pin "6") (pinfunction "6_6") (pintype "passive"))
      (node (ref "XT1") (pin "2") (pintype "passive"))
      (node (ref "XT2") (pin "2") (pintype "passive"))
      (node (ref "XT3") (pin "2") (pinfunction "2_2") (pintype "passive"))
      (node (ref "XT4") (pin "2") (pinfunction "2_2") (pintype "passive"))
    )
    (net (code "102") (name "Net-(C10-Pad2)") (class "Default")
      (node (ref "C10") (pin "2") (pinfunction "2_2") (pintype "passive"))
      (node (ref "R9") (pin "1") (pinfunction "1_1") (pintype "passive"))
      (node (ref "ZQ1") (pin "1") (pinfunction "1_1") (pintype "passive"))
    )
    (net (code "103") (name "Net-(C12-+)") (class "Default")
      (node (ref "C12") (pin "1") (pinfunction "+_1") (pintype "passive"))
      (node (ref "C13") (pin "1") (pinfunction "1_1") (pintype "passive"))
      (node (ref "DD1") (pin "22") (pinfunction "VDDA_22") (pintype "power_in"))
      (node (ref "L3") (pin "2") (pinfunction "2_2") (pintype "passive"))
    )
    (net (code "104") (name "Net-(DD1-VREF+)") (class "Default")
      (node (ref "C14") (pin "2") (pinfunction "2_2") (pintype "passive"))
      (node (ref "DD1") (pin "21") (pinfunction "VREF+_21") (pintype "power_in"))
      (node (ref "R13") (pin "1") (pinfunction "1_1") (pintype "passive"))
    )
    (net (code "105") (name "Net-(DD2-CANH)") (class "Default")
      (node (ref "DD2") (pin "7") (pinfunction "CANH_7") (pintype "passive"))
      (node (ref "X15") (pin "1") (pinfunction "1_1") (pintype "passive"))
      (node (ref "XT3") (pin "1") (pinfunction "1_1") (pintype "passive"))
    )
    (net (code "106") (name "Net-(DD2-CANL)") (class "Default")
      (node (ref "DD2") (pin "6") (pinfunction "CANL_6") (pintype "passive"))
      (node (ref "R38") (pin "1") (pinfunction "1_1") (pintype "passive"))
      (node (ref "XT3") (pin "3") (pinfunction "3_3") (pintype "passive"))
    )
    (net (code "107") (name "Net-(DD2-Rs)") (class "Default")
      (node (ref "DD2") (pin "8") (pinfunction "Rs_8") (pintype "passive"))
      (node (ref "R37") (pin "1") (pinfunction "1_1") (pintype "passive"))
      (node (ref "X13") (pin "2") (pinfunction "2_2") (pintype "passive"))
    )
    (net (code "108") (name "Net-(DD3-CANH)") (class "Default")
      (node (ref "DD3") (pin "7") (pinfunction "CANH_7") (pintype "passive"))
      (node (ref "X16") (pin "1") (pinfunction "1_1") (pintype "passive"))
      (node (ref "XT4") (pin "1") (pinfunction "1_1") (pintype "passive"))
    )
    (net (code "109") (name "Net-(DD3-CANL)") (class "Default")
      (node (ref "DD3") (pin "6") (pinfunction "CANL_6") (pintype "passive"))
      (node (ref "R40") (pin "1") (pinfunction "1_1") (pintype "passive"))
      (node (ref "XT4") (pin "3") (pinfunction "3_3") (pintype "passive"))
    )
    (net (code "110") (name "Net-(DD3-Rs)") (class "Default")
      (node (ref "DD3") (pin "8") (pinfunction "Rs_8") (pintype "passive"))
      (node (ref "R39") (pin "1") (pinfunction "1_1") (pintype "passive"))
      (node (ref "X14") (pin "2") (pinfunction "2_2") (pintype "passive"))
    )
    (net (code "111") (name "Net-(E1-Pad1)") (class "Default")
      (node (ref "E1") (pin "1") (pinfunction "1_1") (pintype "passive"))
      (node (ref "X10") (pin "3") (pinfunction "3_3") (pintype "passive"))
    )
    (net (code "112") (name "Net-(L1-Pad1)") (class "Default")
      (node (ref "L1") (pin "1") (pinfunction "1_1") (pintype "passive"))
      (node (ref "XP3") (pin "1") (pinfunction "1_1") (pintype "passive"))
    )
    (net (code "113") (name "Net-(L2-Pad1)") (class "Default")
      (node (ref "L2") (pin "1") (pinfunction "1_1") (pintype "passive"))
      (node (ref "XP3") (pin "3") (pinfunction "3_3") (pintype "passive"))
    )
    (net (code "114") (name "Net-(R2-Pad2)") (class "Default")
      (node (ref "R2") (pin "2") (pinfunction "2_2") (pintype "passive"))
      (node (ref "XP1") (pin "19") (pinfunction "19_19") (pintype "passive"))
    )
    (net (code "115") (name "Net-(R4-Pad2)") (class "Default")
      (node (ref "R4") (pin "2") (pinfunction "2_2") (pintype "passive"))
      (node (ref "XP1") (pin "17") (pinfunction "17_17") (pintype "passive"))
    )
    (net (code "116") (name "Net-(R10-Pad1)") (class "Default")
      (node (ref "R10") (pin "1") (pinfunction "1_1") (pintype "passive"))
      (node (ref "X7") (pin "2") (pinfunction "2_2") (pintype "passive"))
    )
    (net (code "117") (name "Net-(R11-Pad1)") (class "Default")
      (node (ref "R11") (pin "1") (pinfunction "1_1") (pintype "passive"))
      (node (ref "X9") (pin "2") (pinfunction "2_2") (pintype "passive"))
    )
    (net (code "118") (name "Net-(R19-Pad1)") (class "Default")
      (node (ref "R19") (pin "1") (pinfunction "1_1") (pintype "passive"))
      (node (ref "XS1") (pin "5") (pinfunction "5_5") (pintype "passive"))
    )
    (net (code "119") (name "Net-(R20-Pad1)") (class "Default")
      (node (ref "R20") (pin "1") (pinfunction "1_1") (pintype "passive"))
      (node (ref "XS1") (pin "8") (pinfunction "8_8") (pintype "passive"))
    )
    (net (code "120") (name "Net-(R21-Pad1)") (class "Default")
      (node (ref "R21") (pin "1") (pinfunction "1_1") (pintype "passive"))
      (node (ref "XS1") (pin "1") (pinfunction "1_1") (pintype "passive"))
    )
    (net (code "121") (name "Net-(R22-Pad1)") (class "Default")
      (node (ref "R22") (pin "1") (pinfunction "1_1") (pintype "passive"))
      (node (ref "XS1") (pin "2") (pinfunction "2_2") (pintype "passive"))
    )
    (net (code "122") (name "Net-(R23-Pad1)") (class "Default")
      (node (ref "R23") (pin "1") (pinfunction "1_1") (pintype "passive"))
      (node (ref "XS1") (pin "7") (pinfunction "7_7") (pintype "passive"))
    )
    (net (code "123") (name "Net-(R24-Pad1)") (class "Default")
      (node (ref "R24") (pin "1") (pinfunction "1_1") (pintype "passive"))
      (node (ref "XS1") (pin "10") (pinfunction "10_10") (pintype "passive"))
    )
    (net (code "124") (name "Net-(R25-Pad1)") (class "Default")
      (node (ref "R25") (pin "1") (pinfunction "1_1") (pintype "passive"))
      (node (ref "XS1") (pin "11") (pinfunction "11_11") (pintype "passive"))
    )
    (net (code "125") (name "Net-(R26-Pad2)") (class "Default")
      (node (ref "R26") (pin "2") (pinfunction "2_2") (pintype "passive"))
      (node (ref "XS1") (pin "9") (pinfunction "9_9") (pintype "passive"))
    )
    (net (code "126") (name "Net-(R33-Pad2)") (class "Default")
      (node (ref "R33") (pin "2") (pinfunction "2_2") (pintype "passive"))
      (node (ref "X13") (pin "3") (pinfunction "3_3") (pintype "passive"))
    )
    (net (code "127") (name "Net-(R34-Pad2)") (class "Default")
      (node (ref "R34") (pin "2") (pinfunction "2_2") (pintype "passive"))
      (node (ref "X14") (pin "3") (pinfunction "3_3") (pintype "passive"))
    )
    (net (code "128") (name "Net-(R36-Pad1)") (class "Default")
      (node (ref "R36") (pin "1") (pinfunction "1_1") (pintype "passive"))
      (node (ref "XS2") (pin "8") (pinfunction "8_8") (pintype "passive"))
    )
    (net (code "129") (name "Net-(R38-Pad2)") (class "Default")
      (node (ref "R38") (pin "2") (pinfunction "2_2") (pintype "passive"))
      (node (ref "X15") (pin "2") (pinfunction "2_2") (pintype "passive"))
    )
    (net (code "130") (name "Net-(R40-Pad2)") (class "Default")
      (node (ref "R40") (pin "2") (pinfunction "2_2") (pintype "passive"))
      (node (ref "X16") (pin "2") (pinfunction "2_2") (pintype "passive"))
    )
    (net (code "131") (name "Net-(R41-Pad1)") (class "Default")
      (node (ref "R41") (pin "1") (pinfunction "1_1") (pintype "passive"))
      (node (ref "XS2") (pin "9") (pinfunction "9_9") (pintype "passive"))
    )
    (net (code "132") (name "Net-(X1-Pad2)") (class "Default")
      (node (ref "X1") (pin "2") (pinfunction "2_2") (pintype "passive"))
      (node (ref "XP2") (pin "17") (pinfunction "17_17") (pintype "passive"))
    )
    (net (code "133") (name "Net-(X2-Pad2)") (class "Default")
      (node (ref "X2") (pin "2") (pinfunction "2_2") (pintype "passive"))
      (node (ref "XP2") (pin "19") (pinfunction "19_19") (pintype "passive"))
    )
    (net (code "134") (name "Net-(X11-Pad2)") (class "Default")
      (node (ref "X11") (pin "2") (pinfunction "2_2") (pintype "passive"))
      (node (ref "XS2") (pin "10") (pinfunction "10_10") (pintype "passive"))
      (node (ref "XS3") (pin "9") (pinfunction "9_9") (pintype "passive"))
    )
    (net (code "135") (name "Net-(X12-Pad2)") (class "Default")
      (node (ref "X12") (pin "2") (pinfunction "2_2") (pintype "passive"))
      (node (ref "XS2") (pin "11") (pinfunction "11_11") (pintype "passive"))
    )
    (net (code "136") (name "unconnected-(DD1-NC-Pad73)") (class "Default")
      (node (ref "DD1") (pin "73") (pinfunction "NC_73") (pintype "passive"))
    )
    (net (code "137") (name "unconnected-(DD2-Vref-Pad5)") (class "Default")
      (node (ref "DD2") (pin "5") (pinfunction "Vref_5") (pintype "passive"))
    )
    (net (code "138") (name "unconnected-(DD3-Vref-Pad5)") (class "Default")
      (node (ref "DD3") (pin "5") (pinfunction "Vref_5") (pintype "passive"))
    )
    (net (code "139") (name "unconnected-(XP1-Pad11)") (class "Default")
      (node (ref "XP1") (pin "11") (pinfunction "11_11") (pintype "passive"))
    )
    (net (code "140") (name "unconnected-(XP3-Pad4)") (class "Default")
      (node (ref "XP3") (pin "4") (pinfunction "4_4") (pintype "passive"))
    )
    (net (code "141") (name "unconnected-(XP3-Pad5)") (class "Default")
      (node (ref "XP3") (pin "5") (pinfunction "5_5") (pintype "passive"))
    )
    (net (code "142") (name "unconnected-(XP3-Pad6)") (class "Default")
      (node (ref "XP3") (pin "6") (pinfunction "6_6") (pintype "passive"))
    )
    (net (code "143") (name "unconnected-(XP6-Pad3)") (class "Default")
      (node (ref "XP6") (pin "3") (pinfunction "3_3") (pintype "passive"))
    )
    (net (code "144") (name "unconnected-(XP6-Pad4)") (class "Default")
      (node (ref "XP6") (pin "4") (pinfunction "4_4") (pintype "passive"))
    )
    (net (code "145") (name "unconnected-(XS3-Pad1)") (class "Default")
      (node (ref "XS3") (pin "1") (pinfunction "1_1") (pintype "passive"))
    )
    (net (code "146") (name "unconnected-(XS3-Pad8)") (class "Default")
      (node (ref "XS3") (pin "8") (pinfunction "8_8") (pintype "passive"))
    )
  )
)
